# Communication.net
KiCad netlist of a schematic drawn in Altium Designer
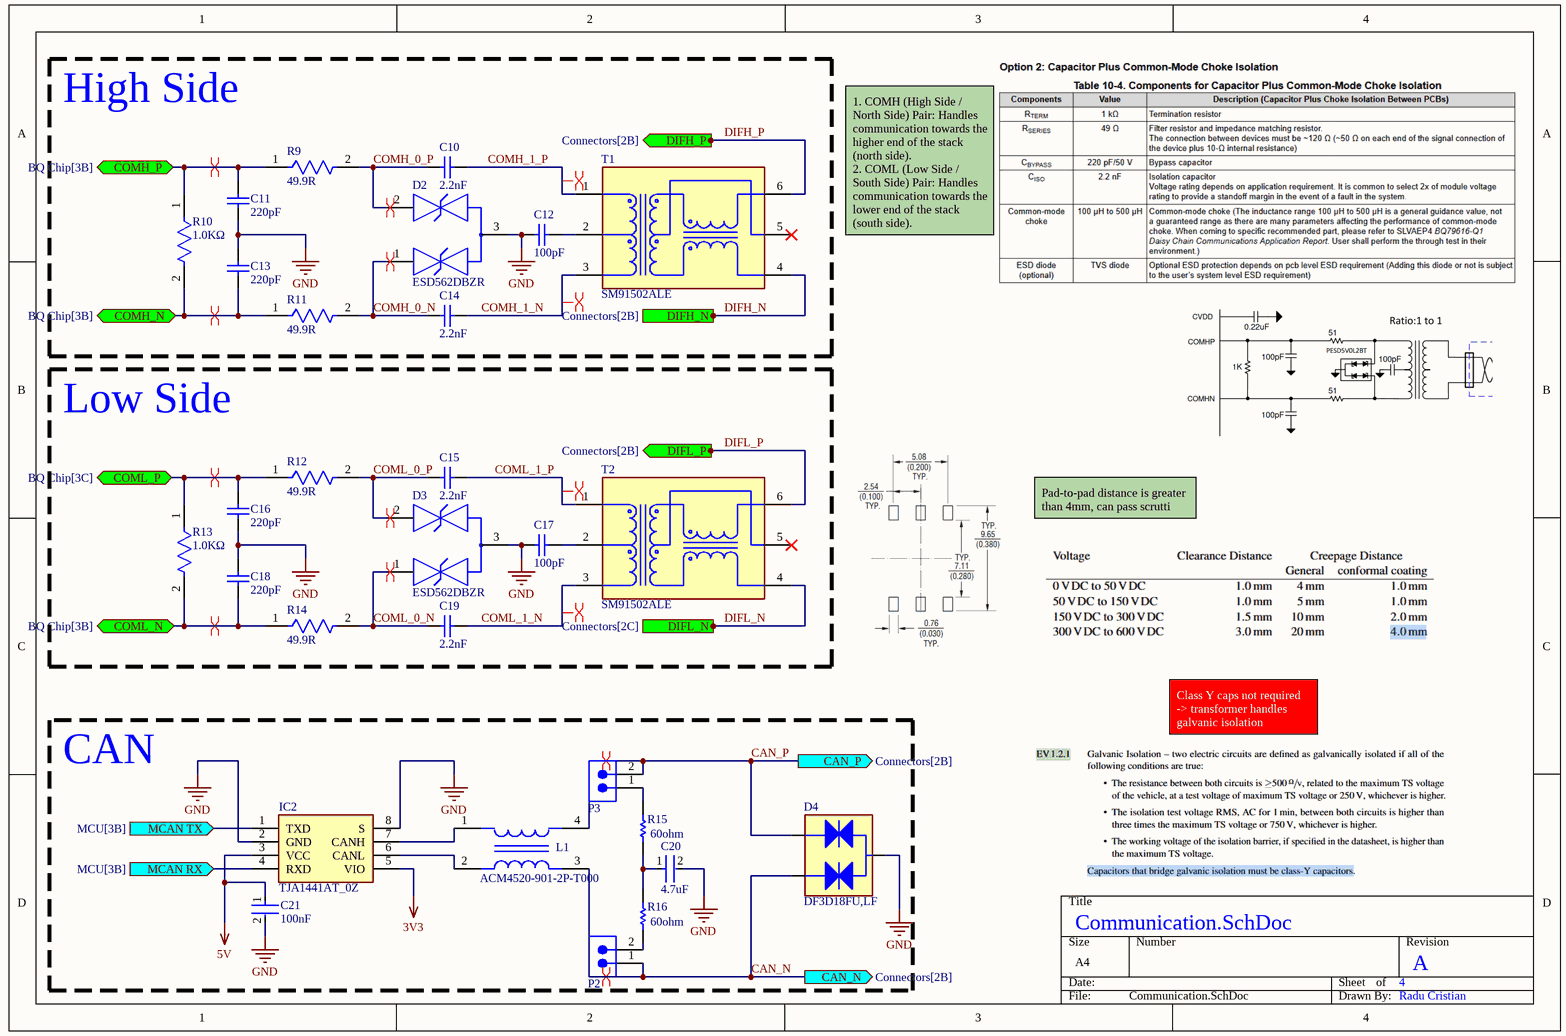
[diagram p0: Communication.SchDoc]

(export (version "E")
  (design (tool "Eeschema 10.0.6"))
  (components
    (comp (ref "C10")
      (value "VJ0603Y222JXBAC")
      (footprint "CAPC1608X92X38ML15T08")
      (fields (field (name "MANUFACTURER") "Vitramon") (field (name "PARAMETER 1") "2.2nF"))
      (libsource (lib "Altium Content Vault") (part "CAP"))
    )
    (comp (ref "C11")
      (value "220pF")
      (footprint "CAPC0603(1608)100_N")
      (description "CAP 220pF 100V ±10% 0603 (1608 Metric) Thickness 1mm SMD")
      (fields (field (name "TOLERANCE") "Â±10%") (field (name "Comment") "CAP 220pF 100V 0603(1608)"))
      (libsource (lib "Altium Content Vault") (part "CAP"))
    )
    (comp (ref "C12")
      (value "06031A101J4T2A")
      (footprint "CAPC1608X90X35NL15T15")
      (fields (field (name "MANUFACTURER") "AVX Interconnect / Elco") (field (name "PARAMETER 1") "100pF"))
      (libsource (lib "Altium Content Vault") (part "CAP"))
    )
    (comp (ref "C13")
      (value "220pF")
      (footprint "CAPC0603(1608)100_N")
      (description "CAP 220pF 100V ±10% 0603 (1608 Metric) Thickness 1mm SMD")
      (fields (field (name "TOLERANCE") "Â±10%") (field (name "Comment") "CAP 220pF 100V 0603(1608)"))
      (libsource (lib "Altium Content Vault") (part "CAP"))
    )
    (comp (ref "C14")
      (value "VJ0603Y222JXBAC")
      (footprint "CAPC1608X92X38ML15T08")
      (fields (field (name "MANUFACTURER") "Vitramon") (field (name "PARAMETER 1") "2.2nF"))
      (libsource (lib "Altium Content Vault") (part "CAP"))
    )
    (comp (ref "C15")
      (value "VJ0603Y222JXBAC")
      (footprint "CAPC1608X92X38ML15T08")
      (fields (field (name "MANUFACTURER") "Vitramon") (field (name "PARAMETER 1") "2.2nF"))
      (libsource (lib "Altium Content Vault") (part "CAP"))
    )
    (comp (ref "C16")
      (value "220pF")
      (footprint "CAPC0603(1608)100_N")
      (description "CAP 220pF 100V ±10% 0603 (1608 Metric) Thickness 1mm SMD")
      (fields (field (name "TOLERANCE") "Â±10%") (field (name "Comment") "CAP 220pF 100V 0603(1608)"))
      (libsource (lib "Altium Content Vault") (part "CAP"))
    )
    (comp (ref "C17")
      (value "06031A101J4T2A")
      (footprint "CAPC1608X90X35NL15T15")
      (fields (field (name "MANUFACTURER") "AVX Interconnect / Elco") (field (name "PARAMETER 1") "100pF"))
      (libsource (lib "Altium Content Vault") (part "CAP"))
    )
    (comp (ref "C18")
      (value "220pF")
      (footprint "CAPC0603(1608)100_N")
      (description "CAP 220pF 100V ±10% 0603 (1608 Metric) Thickness 1mm SMD")
      (fields (field (name "TOLERANCE") "Â±10%") (field (name "Comment") "CAP 220pF 100V 0603(1608)"))
      (libsource (lib "Altium Content Vault") (part "CAP"))
    )
    (comp (ref "C19")
      (value "VJ0603Y222JXBAC")
      (footprint "CAPC1608X92X38ML15T08")
      (fields (field (name "MANUFACTURER") "Vitramon") (field (name "PARAMETER 1") "2.2nF"))
      (libsource (lib "Altium Content Vault") (part "CAP"))
    )
    (comp (ref "C20")
      (value "4.7uF")
      (footprint "FP-C0603C-CF-MFG")
      (description "C0603C 4.7nF Ceramic Multilayer Capacitor; 50 VDC; +125degC; X7R Dielec; +/-5%")
      (fields (field (name "MANUFACTURER PART NUMBER") "C0603C472J5RACTU") (field (name "TOLERANCE") "0.05"))
      (libsource (lib "Altium Content Vault") (part "b4654b650e69147ec39a6b967a45e02"))
    )
    (comp (ref "C21")
      (value "CC0603JRX7R9BB104")
      (footprint "FP-CC0603-DA-IPC_A")
      (description "CAP CER 0.1UF 50V X7R 0603")
      (fields (field (name "CAPACITANCE") "100nF") (field (name "TOLERANCE") "5%"))
      (libsource (lib "Altium Content Vault") (part "02cd4be3c70576c341d710602a673aa"))
    )
    (comp (ref "D2")
      (value "ESD562DBZR")
      (footprint "FP-DBZ0003A-MFG")
      (description "ESD562DBZR Two-channel bidirectional 12V ESD protection diode 3-SOT-23 -40 to 125")
      (libsource (lib "Altium Content Vault") (part "6a230d497ab896455a1178b8499821c"))
    )
    (comp (ref "D3")
      (value "ESD562DBZR")
      (footprint "FP-DBZ0003A-MFG")
      (description "ESD562DBZR Two-channel bidirectional 12V ESD protection diode 3-SOT-23 -40 to 125")
      (libsource (lib "Altium Content Vault") (part "6a230d497ab896455a1178b8499821c"))
    )
    (comp (ref "D4")
      (value "DF3D18FU,LF")
      (footprint "BMS_Master:SOT23-3")
      (description "ESD Suppressors / TVS Diodes ESD Protection Diode Bi-directional type")
      (fields (field (name "MANUFACTURER") "Toshiba"))
      (libsource (lib "BMS_Master") (part "DF3D18FU,LF"))
    )
    (comp (ref "IC2")
      (value "TJA1441AT_0Z")
      (footprint "SamacSys:SOIC127P600X175-8N")
      (description "Integrated Circuit")
      (fields
        (field (name "MANUFACTURER_PART_NUMBER") "TJA1441AT/0Z")
        (field (name "MOUSER PART NUMBER") "771-TJA1441AT/0Z")
      )
      (libsource (lib "*") (part "TJA1441AT_0Z"))
    )
    (comp (ref "L1")
      (value "ACM4520-901-2P-T000")
      (footprint "FP-ACM4520-MFG")
      (description "CMC 2.3A 2LN 900 OHM SMD")
      (libsource (lib "Altium Content Vault") (part "956ec5e206e3d4bf221eee1175b25bc"))
    )
    (comp (ref "P2")
      (value "62000211121")
      (footprint "62000211121")
      (libsource (lib "Altium Content Vault") (part "Header_Male_1R_02P"))
    )
    (comp (ref "P3")
      (value "62000211121")
      (footprint "62000211121")
      (libsource (lib "Altium Content Vault") (part "Header_Male_1R_02P"))
    )
    (comp (ref "R9")
      (value "CRCW060349R9FKECHP")
      (footprint "FP-CRCW0603-HPe3-MFG")
      (description "RES Thick Film, 49.9Ω, 1%, 0.33W, 100ppm/°C, 0603")
      (fields (field (name "TOLERANCE") "1%") (field (name "RESISTANCE") "49.9R"))
      (libsource (lib "Altium Content Vault") (part "1029c3af85768c4190bb7ad29bc67b5"))
    )
    (comp (ref "R10")
      (value "CPF0603F1K0C1")
      (footprint "FP-CPF0603-IPC_C")
      (description "RES SMD 1.0KΩ 1% 1/16W 0603")
      (fields
        (field (name "OCTOPART") "https://octopart.com/cpf0603f1k0c1-te+connectivity-42013134")
        (field (name "TOLERANCE") "1%")
        (field (name "RESISTANCE") "1.0KΩ")
      )
      (libsource (lib "Altium Content Vault") (part "1029c3af85768c4190bb7ad29bc67b5"))
    )
    (comp (ref "R11")
      (value "CRCW060349R9FKECHP")
      (footprint "FP-CRCW0603-HPe3-MFG")
      (description "RES Thick Film, 49.9Ω, 1%, 0.33W, 100ppm/°C, 0603")
      (fields (field (name "TOLERANCE") "1%") (field (name "RESISTANCE") "49.9R"))
      (libsource (lib "Altium Content Vault") (part "1029c3af85768c4190bb7ad29bc67b5"))
    )
    (comp (ref "R12")
      (value "CRCW060349R9FKECHP")
      (footprint "FP-CRCW0603-HPe3-MFG")
      (description "RES Thick Film, 49.9Ω, 1%, 0.33W, 100ppm/°C, 0603")
      (fields (field (name "TOLERANCE") "1%") (field (name "RESISTANCE") "49.9R"))
      (libsource (lib "Altium Content Vault") (part "1029c3af85768c4190bb7ad29bc67b5"))
    )
    (comp (ref "R13")
      (value "CPF0603F1K0C1")
      (footprint "FP-CPF0603-IPC_C")
      (description "RES SMD 1.0KΩ 1% 1/16W 0603")
      (fields
        (field (name "OCTOPART") "https://octopart.com/cpf0603f1k0c1-te+connectivity-42013134")
        (field (name "TOLERANCE") "1%")
        (field (name "RESISTANCE") "1.0KΩ")
      )
      (libsource (lib "Altium Content Vault") (part "1029c3af85768c4190bb7ad29bc67b5"))
    )
    (comp (ref "R14")
      (value "CRCW060349R9FKECHP")
      (footprint "FP-CRCW0603-HPe3-MFG")
      (description "RES Thick Film, 49.9Ω, 1%, 0.33W, 100ppm/°C, 0603")
      (fields (field (name "TOLERANCE") "1%") (field (name "RESISTANCE") "49.9R"))
      (libsource (lib "Altium Content Vault") (part "1029c3af85768c4190bb7ad29bc67b5"))
    )
    (comp (ref "R15")
      (value "ERA3AEB620V")
      (footprint "RESC1608X55X30LL20T20")
      (fields (field (name "MANUFACTURER") "Panasonic") (field (name "PARAMETER 1") "60ohm"))
      (libsource (lib "Altium Content Vault") (part "RES"))
    )
    (comp (ref "R16")
      (value "ERA3AEB620V")
      (footprint "RESC1608X55X30LL20T20")
      (fields (field (name "MANUFACTURER") "Panasonic") (field (name "PARAMETER 1") "60ohm"))
      (libsource (lib "Altium Content Vault") (part "RES"))
    )
    (comp (ref "T1")
      (value "SM91502ALE")
      (footprint "FP-SM91502ALE-MFG")
      (description "BMS XFORMER 1-CH 1000V AECQ +125")
      (fields
        (field (name "MANUFACTURER") "Bourns")
        (field (name "OCTOPART") "https://octopart.com/sm91502ale-bourns-95732123")
      )
      (libsource (lib "Altium Content Vault") (part "554ff5199021d68917f526d8699f58a"))
    )
    (comp (ref "T2")
      (value "SM91502ALE")
      (footprint "FP-SM91502ALE-MFG")
      (description "BMS XFORMER 1-CH 1000V AECQ +125")
      (fields
        (field (name "MANUFACTURER") "Bourns")
        (field (name "OCTOPART") "https://octopart.com/sm91502ale-bourns-95732123")
      )
      (libsource (lib "Altium Content Vault") (part "554ff5199021d68917f526d8699f58a"))
    )
  )
  (nets
    (net (code "1") (name "/CAN_N") (class "Default")
      (node (ref "D4") (pin "1") (pinfunction "1_1") (pintype "passive"))
      (node (ref "L1") (pin "3") (pinfunction "3_3") (pintype "passive"))
      (node (ref "P2") (pin "1") (pinfunction "1_1") (pintype "passive"))
    )
    (net (code "2") (name "/CAN_P") (class "Default")
      (node (ref "D4") (pin "2") (pinfunction "2_2") (pintype "passive"))
      (node (ref "L1") (pin "4") (pinfunction "4_4") (pintype "passive"))
      (node (ref "P3") (pin "2") (pinfunction "2_2") (pintype "passive"))
    )
    (net (code "3") (name "/COMH_0_N") (class "Default")
      (node (ref "C14") (pin "2") (pinfunction "2_2") (pintype "passive"))
      (node (ref "D2") (pin "1") (pinfunction "1_IO_1") (pintype "passive"))
      (node (ref "R11") (pin "2") (pinfunction "2_2") (pintype "passive"))
    )
    (net (code "4") (name "/COMH_0_P") (class "Default")
      (node (ref "C10") (pin "2") (pinfunction "2_2") (pintype "passive"))
      (node (ref "D2") (pin "2") (pinfunction "2_IO_2") (pintype "passive"))
      (node (ref "R9") (pin "2") (pinfunction "2_2") (pintype "passive"))
    )
    (net (code "5") (name "/COMH_1_N") (class "Default")
      (node (ref "C14") (pin "1") (pinfunction "1_1") (pintype "passive"))
      (node (ref "T1") (pin "3") (pinfunction "3_3") (pintype "passive"))
    )
    (net (code "6") (name "/COMH_1_P") (class "Default")
      (node (ref "C10") (pin "1") (pinfunction "1_1") (pintype "passive"))
      (node (ref "T1") (pin "1") (pinfunction "1_1") (pintype "passive"))
    )
    (net (code "7") (name "/COMH_N") (class "Default")
      (node (ref "C13") (pin "2") (pinfunction "2_2") (pintype "passive"))
      (node (ref "R10") (pin "2") (pinfunction "2_2") (pintype "passive"))
      (node (ref "R11") (pin "1") (pinfunction "1_1") (pintype "passive"))
    )
    (net (code "8") (name "/COMH_P") (class "Default")
      (node (ref "C11") (pin "1") (pinfunction "1_1") (pintype "passive"))
      (node (ref "R10") (pin "1") (pinfunction "1_1") (pintype "passive"))
      (node (ref "R9") (pin "1") (pinfunction "1_1") (pintype "passive"))
    )
    (net (code "9") (name "/COML_0_N") (class "Default")
      (node (ref "C19") (pin "2") (pinfunction "2_2") (pintype "passive"))
      (node (ref "D3") (pin "1") (pinfunction "1_IO_1") (pintype "passive"))
      (node (ref "R14") (pin "2") (pinfunction "2_2") (pintype "passive"))
    )
    (net (code "10") (name "/COML_0_P") (class "Default")
      (node (ref "C15") (pin "2") (pinfunction "2_2") (pintype "passive"))
      (node (ref "D3") (pin "2") (pinfunction "2_IO_2") (pintype "passive"))
      (node (ref "R12") (pin "2") (pinfunction "2_2") (pintype "passive"))
    )
    (net (code "11") (name "/COML_1_N") (class "Default")
      (node (ref "C19") (pin "1") (pinfunction "1_1") (pintype "passive"))
      (node (ref "T2") (pin "3") (pinfunction "3_3") (pintype "passive"))
    )
    (net (code "12") (name "/COML_1_P") (class "Default")
      (node (ref "C15") (pin "1") (pinfunction "1_1") (pintype "passive"))
      (node (ref "T2") (pin "1") (pinfunction "1_1") (pintype "passive"))
    )
    (net (code "15") (name "/COML_N") (class "Default")
      (node (ref "C18") (pin "2") (pinfunction "2_2") (pintype "passive"))
      (node (ref "R13") (pin "2") (pinfunction "2_2") (pintype "passive"))
      (node (ref "R14") (pin "1") (pinfunction "1_1") (pintype "passive"))
    )
    (net (code "16") (name "/COML_P") (class "Default")
      (node (ref "C16") (pin "1") (pinfunction "1_1") (pintype "passive"))
      (node (ref "R12") (pin "1") (pinfunction "1_1") (pintype "passive"))
      (node (ref "R13") (pin "1") (pinfunction "1_1") (pintype "passive"))
    )
    (net (code "17") (name "/DIFH_N") (class "Default")
      (node (ref "T1") (pin "4") (pinfunction "4_4") (pintype "passive"))
    )
    (net (code "18") (name "/DIFH_P") (class "Default")
      (node (ref "T1") (pin "6") (pinfunction "6_6") (pintype "passive"))
    )
    (net (code "19") (name "/DIFL_N") (class "Default")
      (node (ref "T2") (pin "4") (pinfunction "4_4") (pintype "passive"))
    )
    (net (code "20") (name "/DIFL_P") (class "Default")
      (node (ref "T2") (pin "6") (pinfunction "6_6") (pintype "passive"))
    )
    (net (code "21") (name "/MCAN RX") (class "Default")
      (node (ref "IC2") (pin "4") (pinfunction "RXD_4") (pintype "passive"))
    )
    (net (code "22") (name "/MCAN TX") (class "Default")
      (node (ref "IC2") (pin "1") (pinfunction "TXD_1") (pintype "passive"))
    )
    (net (code "23") (name "3V3") (class "Default")
      (node (ref "IC2") (pin "5") (pinfunction "VIO_5") (pintype "passive"))
    )
    (net (code "24") (name "5V") (class "Default")
      (node (ref "C21") (pin "1") (pinfunction "1_1") (pintype "passive"))
      (node (ref "IC2") (pin "3") (pinfunction "VCC_3") (pintype "passive"))
    )
    (net (code "25") (name "GND") (class "Default")
      (node (ref "C11") (pin "2") (pinfunction "2_2") (pintype "passive"))
      (node (ref "C12") (pin "1") (pinfunction "1_1") (pintype "passive"))
      (node (ref "C13") (pin "1") (pinfunction "1_1") (pintype "passive"))
      (node (ref "C16") (pin "2") (pinfunction "2_2") (pintype "passive"))
      (node (ref "C17") (pin "1") (pinfunction "1_1") (pintype "passive"))
      (node (ref "C18") (pin "1") (pinfunction "1_1") (pintype "passive"))
      (node (ref "C20") (pin "2") (pinfunction "2_2") (pintype "passive"))
      (node (ref "C21") (pin "2") (pinfunction "2_2") (pintype "passive"))
      (node (ref "D2") (pin "3") (pinfunction "GND_3") (pintype "power_in"))
      (node (ref "D3") (pin "3") (pinfunction "GND_3") (pintype "power_in"))
      (node (ref "D4") (pin "3") (pinfunction "3_3") (pintype "passive"))
      (node (ref "IC2") (pin "2") (pinfunction "GND_2") (pintype "passive"))
      (node (ref "IC2") (pin "8") (pinfunction "S_8") (pintype "passive"))
    )
    (net (code "26") (name "Net-(C12-Pad2)") (class "Default")
      (node (ref "C12") (pin "2") (pinfunction "2_2") (pintype "passive"))
      (node (ref "T1") (pin "2") (pinfunction "2_2") (pintype "passive"))
    )
    (net (code "27") (name "Net-(C17-Pad2)") (class "Default")
      (node (ref "C17") (pin "2") (pinfunction "2_2") (pintype "passive"))
      (node (ref "T2") (pin "2") (pinfunction "2_2") (pintype "passive"))
    )
    (net (code "28") (name "Net-(C20-Pad1)") (class "Default")
      (node (ref "C20") (pin "1") (pinfunction "1_1") (pintype "passive"))
      (node (ref "R15") (pin "1") (pinfunction "1_1") (pintype "passive"))
      (node (ref "R16") (pin "2") (pinfunction "2_2") (pintype "passive"))
    )
    (net (code "29") (name "Net-(IC2-CANH)") (class "Default")
      (node (ref "IC2") (pin "7") (pinfunction "CANH_7") (pintype "passive"))
      (node (ref "L1") (pin "1") (pinfunction "1_1") (pintype "passive"))
    )
    (net (code "30") (name "Net-(IC2-CANL)") (class "Default")
      (node (ref "IC2") (pin "6") (pinfunction "CANL_6") (pintype "passive"))
      (node (ref "L1") (pin "2") (pinfunction "2_2") (pintype "passive"))
    )
    (net (code "31") (name "Net-(P2-Pad2)") (class "Default")
      (node (ref "P2") (pin "2") (pinfunction "2_2") (pintype "passive"))
      (node (ref "R16") (pin "1") (pinfunction "1_1") (pintype "passive"))
    )
    (net (code "32") (name "Net-(P3-Pad1)") (class "Default")
      (node (ref "P3") (pin "1") (pinfunction "1_1") (pintype "passive"))
      (node (ref "R15") (pin "2") (pinfunction "2_2") (pintype "passive"))
    )
    (net (code "33") (name "unconnected-(T1-Pad5)") (class "Default")
      (node (ref "T1") (pin "5") (pinfunction "5_5") (pintype "passive+no_connect"))
    )
    (net (code "34") (name "unconnected-(T2-Pad5)") (class "Default")
      (node (ref "T2") (pin "5") (pinfunction "5_5") (pintype "passive+no_connect"))
    )
  )
)
